# -.net
KiCad netlist of a schematic drawn in Altium Designer
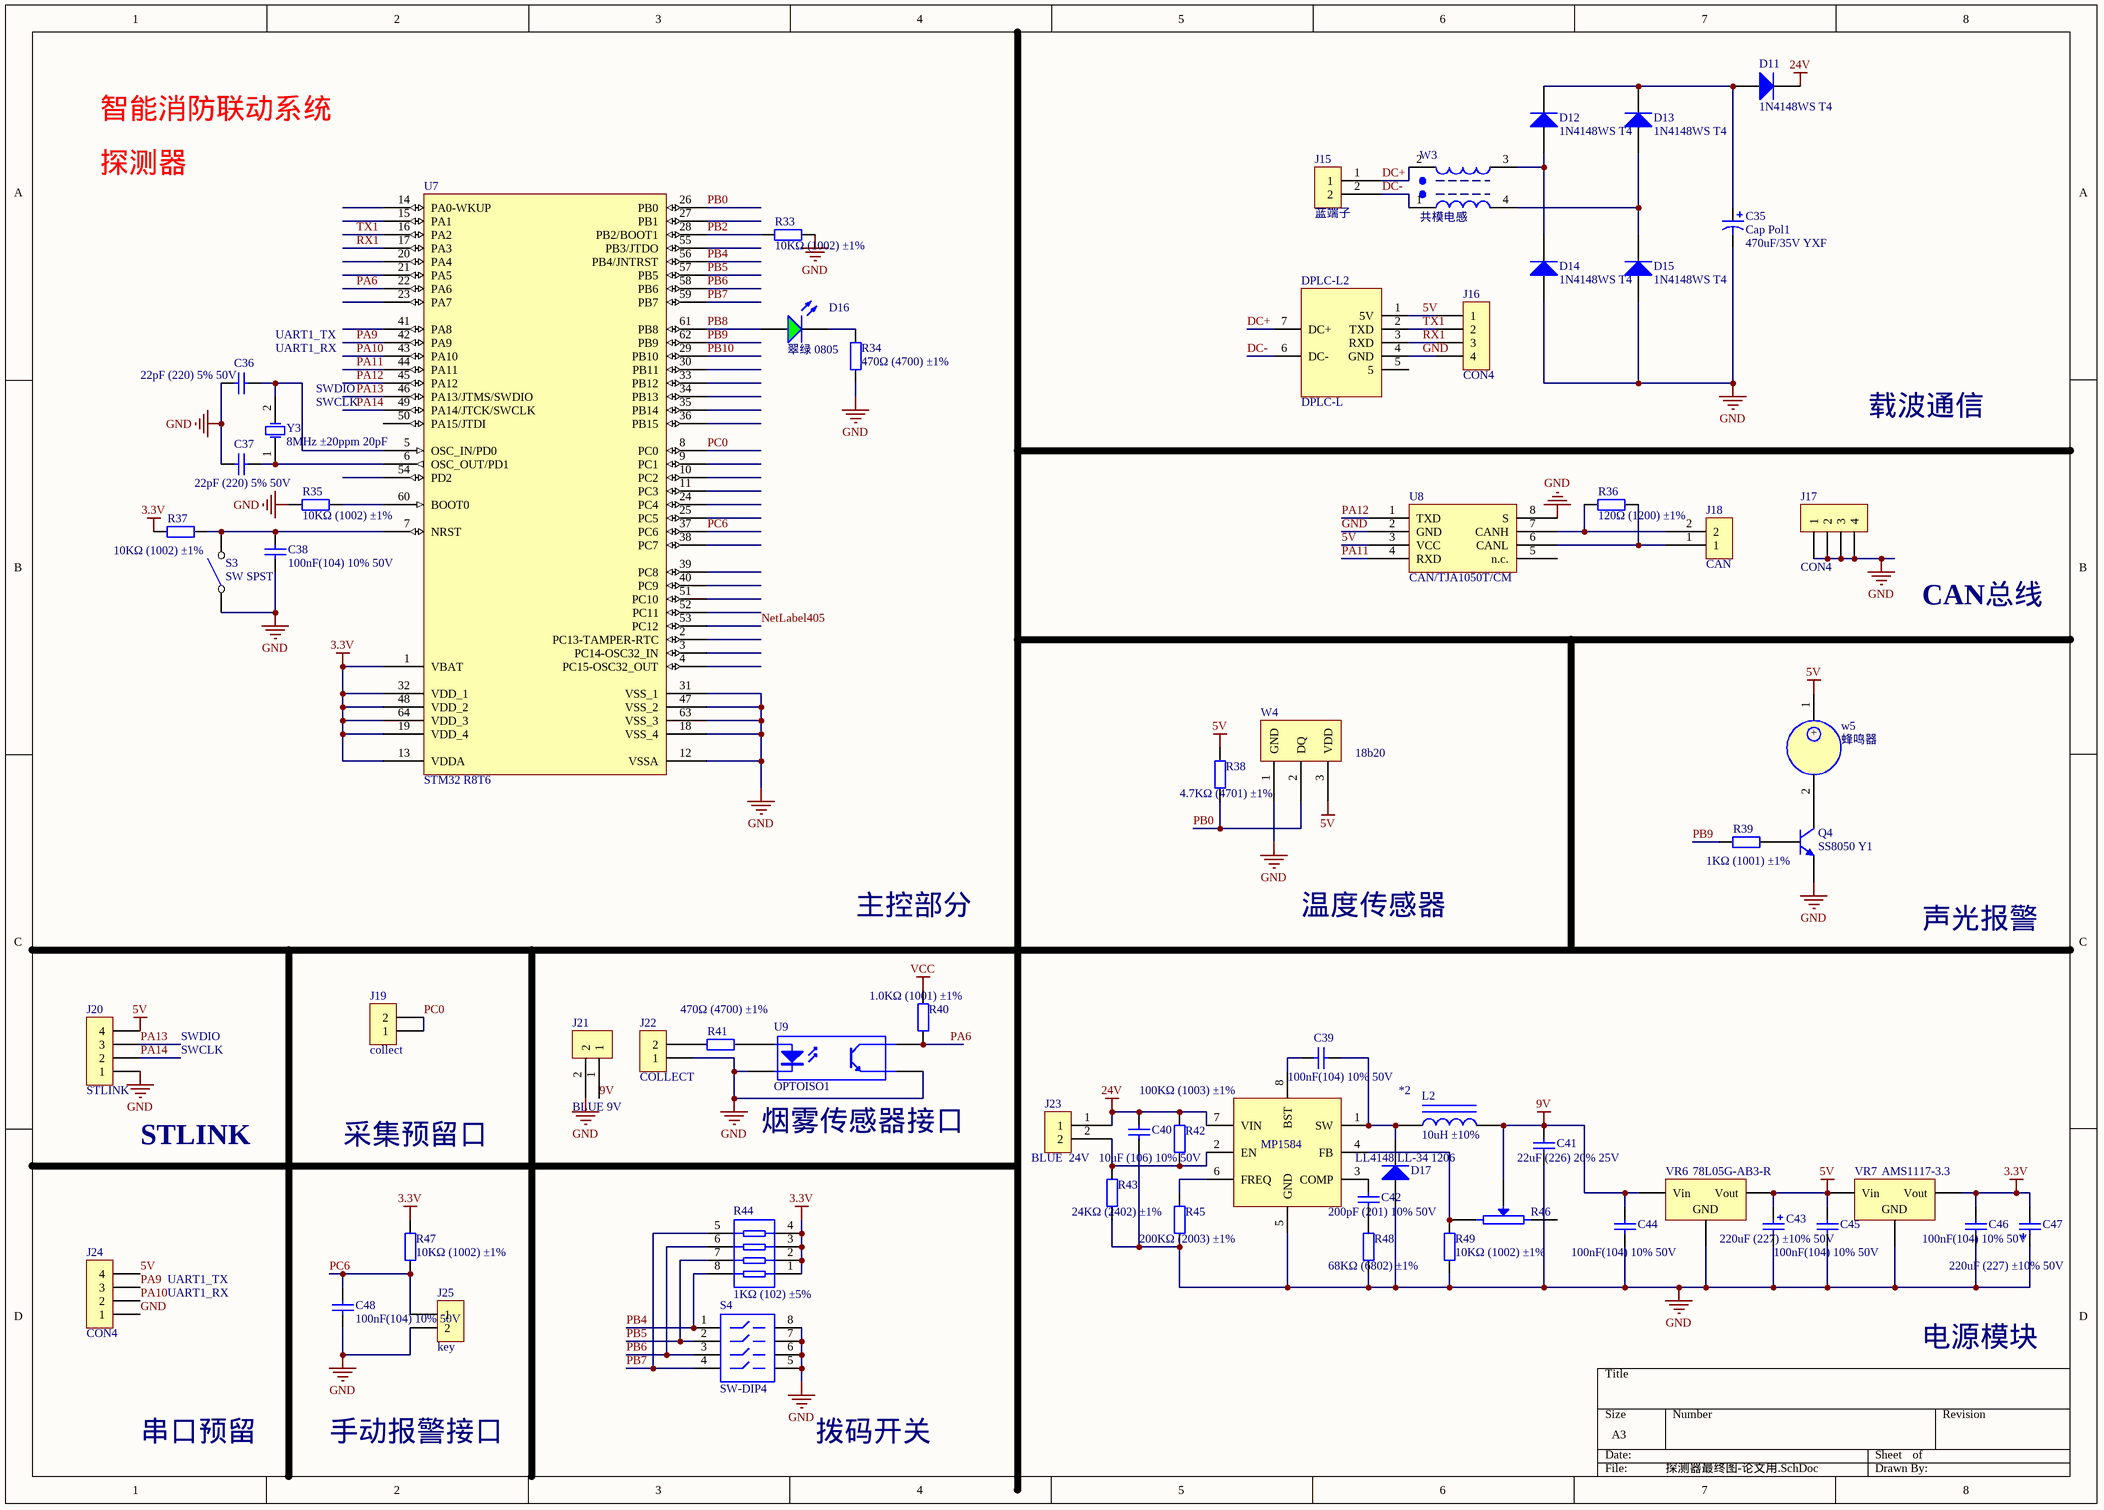
[diagram p0: 探测器最终图-论文用.SchDoc]

(export (version "E")
  (design (tool "Eeschema 10.0.6"))
  (components
    (comp (ref "*2") (value "MP1584") (libsource (lib "毕设原理图封装库") (part "MP1584")))
    (comp (ref "C35")
      (value "Cap Pol1")
      (footprint "RB.2/.4")
      (description "Polarized Capacitor (Radial)")
      (fields (field (name "ALTIUM_VALUE") "470uF/35V YXF") (field (name "PUBLISHER") "Altium Limited"))
      (libsource (lib "Miscellaneous Devices") (part "Cap Pol1"))
    )
    (comp (ref "C36")
      (value "22pF (220) 5% 50V")
      (footprint "LC-0805_C")
      (description "贴片电容")
      (libsource (lib "Miscellaneous Devices LC") (part "0805 22pF (220) 5% 50V"))
    )
    (comp (ref "C37")
      (value "22pF (220) 5% 50V")
      (footprint "LC-0805_C")
      (description "贴片电容")
      (libsource (lib "Miscellaneous Devices LC") (part "0805 22pF (220) 5% 50V"))
    )
    (comp (ref "C38")
      (value "100nF(104) 10% 50V")
      (footprint "LC-0805_C")
      (description "贴片电容")
      (libsource (lib "Miscellaneous Devices LC") (part "0805 100nF(104) 10% 50V"))
    )
    (comp (ref "C39")
      (value "100nF(104) 10% 50V")
      (footprint "LC-0805_C")
      (description "贴片电容")
      (libsource (lib "Miscellaneous Devices LC") (part "0805 100nF(104) 10% 50V"))
    )
    (comp (ref "C40")
      (value "10uF (106) 10% 50V")
      (footprint "LC-1206_C")
      (description "贴片电容")
      (libsource (lib "Miscellaneous Devices LC") (part "1206 10uF (106) 10% 50V"))
    )
    (comp (ref "C41")
      (value "22uF (226) 20% 25V")
      (footprint "LC-0805_C")
      (description "贴片电容")
      (libsource (lib "Miscellaneous Devices LC") (part "0805 22uF (226) 20% 25V"))
    )
    (comp (ref "C42")
      (value "200pF (201) 10% 50V")
      (footprint "LC-0805_C")
      (description "贴片电容")
      (libsource (lib "Miscellaneous Devices LC") (part "0805 200pF (201) 10% 50V"))
    )
    (comp (ref "C43")
      (value "220uF (227) ±10% 50V")
      (footprint "LC-CASE-B_3528")
      (description "钽电容")
      (libsource (lib "Miscellaneous Devices LC") (part "3528 100uF (107) 10% 6.3V"))
    )
    (comp (ref "C44")
      (value "100nF(104) 10% 50V")
      (footprint "LC-0805_C")
      (description "贴片电容")
      (libsource (lib "Miscellaneous Devices LC") (part "0805 100nF(104) 10% 50V"))
    )
    (comp (ref "C45")
      (value "100nF(104) 10% 50V")
      (footprint "LC-0805_C")
      (description "贴片电容")
      (libsource (lib "Miscellaneous Devices LC") (part "0805 100nF(104) 10% 50V"))
    )
    (comp (ref "C46")
      (value "100nF(104) 10% 50V")
      (footprint "LC-0805_C")
      (description "贴片电容")
      (libsource (lib "Miscellaneous Devices LC") (part "0805 100nF(104) 10% 50V"))
    )
    (comp (ref "C47")
      (value "220uF (227) ±10% 50V")
      (footprint "LC-CASE-B_3528")
      (description "钽电容")
      (libsource (lib "Miscellaneous Devices LC") (part "3528 100uF (107) 10% 6.3V"))
    )
    (comp (ref "C48")
      (value "100nF(104) 10% 50V")
      (footprint "LC-0805_C")
      (description "贴片电容")
      (libsource (lib "Miscellaneous Devices LC") (part "0805 100nF(104) 10% 50V"))
    )
    (comp (ref "D11")
      (value "1N4148WS T4")
      (footprint "LC-SOD-323")
      (description "二极管")
      (libsource (lib "Miscellaneous Devices LC") (part "SOD-323 1N4148WS T4"))
    )
    (comp (ref "D12")
      (value "1N4148WS T4")
      (footprint "LC-SOD-323")
      (description "二极管")
      (libsource (lib "Miscellaneous Devices LC") (part "SOD-323 1N4148WS T4"))
    )
    (comp (ref "D13")
      (value "1N4148WS T4")
      (footprint "LC-SOD-323")
      (description "二极管")
      (libsource (lib "Miscellaneous Devices LC") (part "SOD-323 1N4148WS T4"))
    )
    (comp (ref "D14")
      (value "1N4148WS T4")
      (footprint "LC-SOD-323")
      (description "二极管")
      (libsource (lib "Miscellaneous Devices LC") (part "SOD-323 1N4148WS T4"))
    )
    (comp (ref "D15")
      (value "1N4148WS T4")
      (footprint "LC-SOD-323")
      (description "二极管")
      (libsource (lib "Miscellaneous Devices LC") (part "SOD-323 1N4148WS T4"))
    )
    (comp (ref "D16")
      (value "翠绿 0805")
      (footprint "LC-0805_LED_S1")
      (description "发光二极管")
      (libsource (lib "Miscellaneous Devices LC") (part "0805 翠绿"))
    )
    (comp (ref "D17")
      (value "LL4148 LL-34 1206")
      (footprint "LC-LL-34")
      (description "开关二极管")
      (libsource (lib "Miscellaneous Devices LC") (part "LL-34 LL4148 LL-34 1206"))
    )
    (comp (ref "DPLC-L2") (value "DPLC-L") (footprint "DPLC-L") (libsource (lib "毕设原理图封装库") (part "DPLC-L")))
    (comp (ref "J15") (value "蓝端子") (footprint "蓝端子") (libsource (lib "") (part "蓝端子_1")))
    (comp (ref "J16") (value "CON4") (footprint "SIP4") (libsource (lib "") (part "CON4_1")))
    (comp (ref "J17") (value "CON4") (footprint "SIP4") (libsource (lib "") (part "CON4_2")))
    (comp (ref "J18") (value "CAN") (footprint "蓝端子") (libsource (lib "") (part "蓝端子_2")))
    (comp (ref "J19") (value "collect") (footprint "SIP2") (libsource (lib "") (part "CON2_1")))
    (comp (ref "J20") (value "STLINK") (footprint "SIP4") (libsource (lib "毕设原理图封装库") (part "CON4")))
    (comp (ref "J21") (value "BLUE 9V") (footprint "蓝端子") (libsource (lib "毕设原理图封装库") (part "蓝端子")))
    (comp (ref "J22") (value "COLLECT") (footprint "SIP2") (libsource (lib "") (part "CON2_1")))
    (comp (ref "J23") (value "BLUE  24V") (footprint "蓝端子") (libsource (lib "") (part "蓝端子_1")))
    (comp (ref "J24") (value "CON4") (footprint "SIP4") (libsource (lib "毕设原理图封装库") (part "CON4")))
    (comp (ref "J25") (value "key") (footprint "SIP2") (libsource (lib "毕设原理图封装库") (part "CON2")))
    (comp (ref "L2")
      (value "10uH ±10%")
      (footprint "LC-0805_L")
      (description "贴片电感")
      (libsource (lib "Miscellaneous Devices LC") (part "0805 10uH 10%"))
    )
    (comp (ref "Q4")
      (value "SS8050 Y1")
      (footprint "LC-SOT-23(SOT-23-3)")
      (description "三极管")
      (libsource (lib "Miscellaneous Devices LC") (part "SOT-23 SS8050 Y1"))
    )
    (comp (ref "R33")
      (value "10KΩ (1002) ±1%")
      (footprint "LC-0805_R")
      (description "贴片电阻")
      (libsource (lib "") (part "0805 10KΩ (1002) 1%_2"))
    )
    (comp (ref "R34")
      (value "470Ω (4700) ±1%")
      (footprint "LC-0805_R")
      (description "贴片电阻")
      (libsource (lib "Miscellaneous Devices LC") (part "0805 470Ω (4700) 1%"))
    )
    (comp (ref "R35")
      (value "10KΩ (1002) ±1%")
      (footprint "LC-0805_R")
      (description "贴片电阻")
      (libsource (lib "Miscellaneous Devices LC") (part "0805 10KΩ (1002) 1%"))
    )
    (comp (ref "R36")
      (value "120Ω (1200) ±1%")
      (footprint "LC-0805_R")
      (description "贴片电阻")
      (libsource (lib "Miscellaneous Devices LC") (part "0805 120Ω (1200) 1%"))
    )
    (comp (ref "R37")
      (value "10KΩ (1002) ±1%")
      (footprint "LC-0805_R")
      (description "贴片电阻")
      (libsource (lib "Miscellaneous Devices LC") (part "0805 10KΩ (1002) 1%"))
    )
    (comp (ref "R38")
      (value "4.7KΩ (4701) ±1%")
      (footprint "LC-0805_R")
      (description "贴片电阻")
      (libsource (lib "") (part "0805 4.7KΩ (4701) 1%_1"))
    )
    (comp (ref "R39")
      (value "1KΩ (1001) ±1%")
      (footprint "LC-0805_R")
      (description "贴片电阻")
      (libsource (lib "Miscellaneous Devices LC") (part "0805 1KΩ (1001) 1%"))
    )
    (comp (ref "R40")
      (value "1.0KΩ (1001) ±1%")
      (footprint "LC-0805_R")
      (description "贴片电阻")
      (libsource (lib "") (part "0805 4.7KΩ (4701) 1%_1"))
    )
    (comp (ref "R41")
      (value "470Ω (4700) ±1%")
      (footprint "LC-0805_R")
      (description "贴片电阻")
      (libsource (lib "Miscellaneous Devices LC") (part "0805 4.7KΩ (4701) 1%"))
    )
    (comp (ref "R42")
      (value "100KΩ (1003) ±1%")
      (footprint "LC-0805_R")
      (description "贴片电阻")
      (libsource (lib "Miscellaneous Devices LC") (part "0805 100KΩ (1003) 1%"))
    )
    (comp (ref "R43")
      (value "24KΩ (2402) ±1%")
      (footprint "LC-0805_R")
      (description "贴片电阻")
      (libsource (lib "Miscellaneous Devices LC") (part "0805 24KΩ (2402) 1%"))
    )
    (comp (ref "R44")
      (value "1KΩ (102) ±5%")
      (footprint "LC-0603_Rx4")
      (description "贴片排阻")
      (libsource (lib "Miscellaneous Devices LC") (part "0603*4  1KΩ (102) 5%"))
    )
    (comp (ref "R45")
      (value "200KΩ (2003) ±1%")
      (footprint "LC-0805_R")
      (description "贴片电阻")
      (libsource (lib "Miscellaneous Devices LC") (part "0805 200KΩ (2003) 1%"))
    )
    (comp (ref "R46") (value "2") (description "滑变2") (libsource (lib "原理图封装库") (part "POT2")))
    (comp (ref "R47")
      (value "10KΩ (1002) ±1%")
      (footprint "LC-0805_R")
      (description "贴片电阻")
      (libsource (lib "") (part "0805 10KΩ (1002) 1%_1"))
    )
    (comp (ref "R48")
      (value "68KΩ (6802) ±1%")
      (footprint "LC-0805_R")
      (description "贴片电阻")
      (libsource (lib "Miscellaneous Devices LC") (part "0805 68KΩ (6802) 1%"))
    )
    (comp (ref "R49")
      (value "10KΩ (1002) ±1%")
      (footprint "LC-0805_R")
      (description "贴片电阻")
      (libsource (lib "") (part "0805 10KΩ (1002) 1%_1"))
    )
    (comp (ref "S3")
      (value "SW SPST")
      (footprint "单片机小按键")
      (description "单刀单掷开关")
      (libsource (lib "毕设原理图封装库") (part "SW SPST"))
    )
    (comp (ref "S4")
      (value "SW-DIP4")
      (footprint "4位拨码开关")
      (description "4位拨码开关")
      (libsource (lib "毕设原理图封装库") (part "SW-DIP4"))
    )
    (comp (ref "U7")
      (value "STM32 R8T6")
      (footprint "LC-LQFP-64_10x10x05P")
      (libsource (lib "毕设原理图封装库") (part "STM32 R8T6"))
    )
    (comp (ref "U8")
      (value "CAN/TJA1050T/CM")
      (footprint "LC-SOIC-8_150mil")
      (description "CAN")
      (libsource (lib "Miscellaneous Devices LC") (part "CAN/TJA1050T/CM"))
    )
    (comp (ref "U9")
      (value "OPTOISO1")
      (footprint "LC-SOP-4_P2.54")
      (description "光电对管")
      (libsource (lib "毕设原理图封装库") (part "OPTOISO1"))
    )
    (comp (ref "VR6")
      (value "78L05G-AB3-R")
      (footprint "LC-SOT-89(SOT-89-3)")
      (description "低压差线性稳压(LDO)")
      (libsource (lib "Miscellaneous Devices LC") (part "SOT-89 78L05G-AB3-R"))
    )
    (comp (ref "VR7")
      (value "AMS1117-3.3")
      (footprint "LC-SOT-223")
      (description "低压差线性稳压(LDO)")
      (libsource (lib "Miscellaneous Devices LC") (part "SOT-223 AMS1117-3.3"))
    )
    (comp (ref "W3") (value "共模电感") (footprint "共模电感") (libsource (lib "毕设原理图封装库") (part "共模电感")))
    (comp (ref "W4") (value "18b20") (footprint "DS18B20") (libsource (lib "毕设原理图封装库") (part "18b20")))
    (comp (ref "w5") (value "蜂鸣器") (footprint "蜂鸣器") (libsource (lib "毕设原理图封装库") (part "蜂鸣器")))
    (comp (ref "Y3")
      (value "8MHz ±20ppm 20pF")
      (footprint "LC-SMD-5032_2P")
      (description "贴片晶振")
      (libsource (lib "Miscellaneous Devices LC") (part "SMD-5032_2P 8MHz 20ppm 20pF"))
    )
  )
  (nets
    (net (code "1") (name "/DC+") (class "Default")
      (node (ref "DPLC-L2") (pin "7") (pinfunction "DC+_7") (pintype "passive"))
      (node (ref "J15") (pin "1") (pinfunction "1_1") (pintype "passive"))
      (node (ref "W3") (pin "2") (pinfunction "2_2") (pintype "passive"))
    )
    (net (code "2") (name "/DC-") (class "Default")
      (node (ref "DPLC-L2") (pin "6") (pinfunction "DC-_6") (pintype "passive"))
      (node (ref "J15") (pin "2") (pinfunction "2_2") (pintype "passive"))
      (node (ref "W3") (pin "1") (pinfunction "1_1") (pintype "passive"))
    )
    (net (code "3") (name "/NetLabel405") (class "Default")
      (node (ref "U7") (pin "53") (pinfunction "PC12_53") (pintype "bidirectional"))
    )
    (net (code "4") (name "/PA6") (class "Default")
      (node (ref "R40") (pin "1") (pinfunction "1_1") (pintype "passive"))
      (node (ref "U7") (pin "22") (pinfunction "PA6_22") (pintype "bidirectional"))
      (node (ref "U9") (pin "4") (pinfunction "C_4") (pintype "passive"))
    )
    (net (code "5") (name "/PA9") (class "Default")
      (node (ref "J24") (pin "3") (pinfunction "3_3") (pintype "passive"))
      (node (ref "U7") (pin "42") (pinfunction "PA9_42") (pintype "bidirectional"))
    )
    (net (code "6") (name "/PA10") (class "Default")
      (node (ref "J24") (pin "2") (pinfunction "2_2") (pintype "passive"))
      (node (ref "U7") (pin "43") (pinfunction "PA10_43") (pintype "bidirectional"))
    )
    (net (code "7") (name "/PA11") (class "Default")
      (node (ref "U7") (pin "44") (pinfunction "PA11_44") (pintype "bidirectional"))
      (node (ref "U8") (pin "4") (pinfunction "RXD_4") (pintype "passive"))
    )
    (net (code "8") (name "/PA12") (class "Default")
      (node (ref "U7") (pin "45") (pinfunction "PA12_45") (pintype "bidirectional"))
      (node (ref "U8") (pin "1") (pinfunction "TXD_1") (pintype "passive"))
    )
    (net (code "9") (name "/PA13") (class "Default")
      (node (ref "J20") (pin "3") (pinfunction "3_3") (pintype "passive"))
      (node (ref "U7") (pin "46") (pinfunction "PA13/JTMS/SWDIO_46") (pintype "bidirectional"))
    )
    (net (code "10") (name "/PA14") (class "Default")
      (node (ref "J20") (pin "2") (pinfunction "2_2") (pintype "passive"))
      (node (ref "U7") (pin "49") (pinfunction "PA14/JTCK/SWCLK_49") (pintype "bidirectional"))
    )
    (net (code "11") (name "/PB0") (class "Default")
      (node (ref "R38") (pin "1") (pinfunction "1_1") (pintype "passive"))
      (node (ref "U7") (pin "26") (pinfunction "PB0_26") (pintype "bidirectional"))
      (node (ref "W4") (pin "2") (pinfunction "DQ_2") (pintype "passive"))
    )
    (net (code "12") (name "/PB2") (class "Default")
      (node (ref "R33") (pin "2") (pinfunction "2_2") (pintype "passive"))
      (node (ref "U7") (pin "28") (pinfunction "PB2/BOOT1_28") (pintype "bidirectional"))
    )
    (net (code "13") (name "/PB4") (class "Default")
      (node (ref "R44") (pin "8") (pinfunction "8_8") (pintype "passive"))
      (node (ref "S4") (pin "1") (pinfunction "1_1") (pintype "passive"))
      (node (ref "U7") (pin "56") (pinfunction "PB4/JNTRST_56") (pintype "bidirectional"))
    )
    (net (code "14") (name "/PB5") (class "Default")
      (node (ref "R44") (pin "7") (pinfunction "7_7") (pintype "passive"))
      (node (ref "S4") (pin "2") (pinfunction "2_2") (pintype "passive"))
      (node (ref "U7") (pin "57") (pinfunction "PB5_57") (pintype "bidirectional"))
    )
    (net (code "15") (name "/PB6") (class "Default")
      (node (ref "R44") (pin "6") (pinfunction "6_6") (pintype "passive"))
      (node (ref "S4") (pin "3") (pinfunction "3_3") (pintype "passive"))
      (node (ref "U7") (pin "58") (pinfunction "PB6_58") (pintype "bidirectional"))
    )
    (net (code "16") (name "/PB7") (class "Default")
      (node (ref "R44") (pin "5") (pinfunction "5_5") (pintype "passive"))
      (node (ref "S4") (pin "4") (pinfunction "4_4") (pintype "passive"))
      (node (ref "U7") (pin "59") (pinfunction "PB7_59") (pintype "bidirectional"))
    )
    (net (code "17") (name "/PB8") (class "Default")
      (node (ref "D16") (pin "A") (pinfunction "A_A") (pintype "passive"))
      (node (ref "U7") (pin "61") (pinfunction "PB8_61") (pintype "bidirectional"))
    )
    (net (code "18") (name "/PB9") (class "Default")
      (node (ref "R39") (pin "1") (pinfunction "1_1") (pintype "passive"))
      (node (ref "U7") (pin "62") (pinfunction "PB9_62") (pintype "bidirectional"))
    )
    (net (code "19") (name "/PB10") (class "Default")
      (node (ref "U7") (pin "29") (pinfunction "PB10_29") (pintype "bidirectional"))
    )
    (net (code "20") (name "/PC0") (class "Default")
      (node (ref "J19") (pin "1") (pinfunction "1_1") (pintype "passive"))
      (node (ref "J19") (pin "2") (pinfunction "2_2") (pintype "passive"))
      (node (ref "U7") (pin "8") (pinfunction "PC0_8") (pintype "bidirectional"))
    )
    (net (code "21") (name "/PC6") (class "Default")
      (node (ref "C48") (pin "2") (pinfunction "2_2") (pintype "passive"))
      (node (ref "J25") (pin "1") (pinfunction "1_1") (pintype "passive"))
      (node (ref "R47") (pin "1") (pinfunction "1_1") (pintype "passive"))
      (node (ref "U7") (pin "37") (pinfunction "PC6_37") (pintype "bidirectional"))
    )
    (net (code "22") (name "/RX1") (class "Default")
      (node (ref "DPLC-L2") (pin "3") (pinfunction "RXD_3") (pintype "passive"))
      (node (ref "J16") (pin "3") (pinfunction "3_3") (pintype "passive"))
      (node (ref "U7") (pin "17") (pinfunction "PA3_17") (pintype "bidirectional"))
    )
    (net (code "23") (name "/TX1") (class "Default")
      (node (ref "DPLC-L2") (pin "2") (pinfunction "TXD_2") (pintype "passive"))
      (node (ref "J16") (pin "2") (pinfunction "2_2") (pintype "passive"))
      (node (ref "U7") (pin "16") (pinfunction "PA2_16") (pintype "bidirectional"))
    )
    (net (code "24") (name "3.3V") (class "Default")
      (node (ref "C46") (pin "1") (pinfunction "1_1") (pintype "passive"))
      (node (ref "C47") (pin "2") (pinfunction "2_2") (pintype "passive"))
      (node (ref "R37") (pin "1") (pinfunction "1_1") (pintype "passive"))
      (node (ref "R44") (pin "1") (pinfunction "1_1") (pintype "passive"))
      (node (ref "R44") (pin "2") (pinfunction "2_2") (pintype "passive"))
      (node (ref "R44") (pin "3") (pinfunction "3_3") (pintype "passive"))
      (node (ref "R44") (pin "4") (pinfunction "4_4") (pintype "passive"))
      (node (ref "R47") (pin "2") (pinfunction "2_2") (pintype "passive"))
      (node (ref "U7") (pin "1") (pinfunction "VBAT_1") (pintype "power_in"))
      (node (ref "U7") (pin "13") (pinfunction "VDDA_13") (pintype "power_in"))
      (node (ref "U7") (pin "19") (pinfunction "VDD_4_19") (pintype "power_in"))
      (node (ref "U7") (pin "32") (pinfunction "VDD_1_32") (pintype "power_in"))
      (node (ref "U7") (pin "48") (pinfunction "VDD_2_48") (pintype "power_in"))
      (node (ref "U7") (pin "64") (pinfunction "VDD_3_64") (pintype "power_in"))
      (node (ref "VR7") (pin "2") (pinfunction "Vout_2") (pintype "passive"))
    )
    (net (code "25") (name "5V") (class "Default")
      (node (ref "C43") (pin "1") (pinfunction "1_1") (pintype "passive"))
      (node (ref "C45") (pin "2") (pinfunction "2_2") (pintype "passive"))
      (node (ref "DPLC-L2") (pin "1") (pinfunction "5V_1") (pintype "passive"))
      (node (ref "J16") (pin "1") (pinfunction "1_1") (pintype "passive"))
      (node (ref "J20") (pin "4") (pinfunction "4_4") (pintype "passive"))
      (node (ref "J24") (pin "4") (pinfunction "4_4") (pintype "passive"))
      (node (ref "R38") (pin "2") (pinfunction "2_2") (pintype "passive"))
      (node (ref "U8") (pin "3") (pinfunction "VCC_3") (pintype "passive"))
      (node (ref "VR6") (pin "3") (pinfunction "Vout_3") (pintype "passive"))
      (node (ref "VR7") (pin "3") (pinfunction "Vin_3") (pintype "passive"))
      (node (ref "W4") (pin "3") (pinfunction "VDD_3") (pintype "passive"))
      (node (ref "w5") (pin "1") (pinfunction "+_1") (pintype "passive"))
    )
    (net (code "26") (name "9V") (class "Default")
      (node (ref "C41") (pin "2") (pinfunction "2_2") (pintype "passive"))
      (node (ref "C44") (pin "2") (pinfunction "2_2") (pintype "passive"))
      (node (ref "J21") (pin "1") (pinfunction "1_1") (pintype "passive"))
      (node (ref "L2") (pin "2") (pinfunction "2_2") (pintype "passive"))
      (node (ref "R46") (pin "3") (pinfunction "W_3") (pintype "passive"))
      (node (ref "VR6") (pin "1") (pinfunction "Vin_1") (pintype "passive"))
    )
    (net (code "27") (name "24V") (class "Default")
      (node (ref "*2") (pin "7") (pinfunction "VIN_7") (pintype "passive"))
      (node (ref "C40") (pin "2") (pinfunction "2_2") (pintype "passive"))
      (node (ref "D11") (pin "2") (pinfunction "K_2") (pintype "passive"))
      (node (ref "J23") (pin "1") (pinfunction "1_1") (pintype "passive"))
      (node (ref "R42") (pin "2") (pinfunction "2_2") (pintype "passive"))
    )
    (net (code "28") (name "GND") (class "Default")
      (node (ref "*2") (pin "5") (pinfunction "GND_5") (pintype "passive"))
      (node (ref "C35") (pin "2") (pinfunction "2_2") (pintype "passive"))
      (node (ref "C36") (pin "1") (pinfunction "1_1") (pintype "passive"))
      (node (ref "C37") (pin "1") (pinfunction "1_1") (pintype "passive"))
      (node (ref "C38") (pin "1") (pinfunction "1_1") (pintype "passive"))
      (node (ref "C40") (pin "1") (pinfunction "1_1") (pintype "passive"))
      (node (ref "C41") (pin "1") (pinfunction "1_1") (pintype "passive"))
      (node (ref "C43") (pin "2") (pinfunction "2_2") (pintype "passive"))
      (node (ref "C44") (pin "1") (pinfunction "1_1") (pintype "passive"))
      (node (ref "C45") (pin "1") (pinfunction "1_1") (pintype "passive"))
      (node (ref "C46") (pin "2") (pinfunction "2_2") (pintype "passive"))
      (node (ref "C47") (pin "1") (pinfunction "1_1") (pintype "passive"))
      (node (ref "C48") (pin "1") (pinfunction "1_1") (pintype "passive"))
      (node (ref "D14") (pin "1") (pinfunction "A_1") (pintype "passive"))
      (node (ref "D15") (pin "1") (pinfunction "A_1") (pintype "passive"))
      (node (ref "D17") (pin "1") (pinfunction "A_1") (pintype "passive"))
      (node (ref "DPLC-L2") (pin "4") (pinfunction "GND_4") (pintype "passive"))
      (node (ref "J16") (pin "4") (pinfunction "4_4") (pintype "passive"))
      (node (ref "J17") (pin "1") (pinfunction "1_1") (pintype "passive"))
      (node (ref "J17") (pin "2") (pinfunction "2_2") (pintype "passive"))
      (node (ref "J17") (pin "3") (pinfunction "3_3") (pintype "passive"))
      (node (ref "J17") (pin "4") (pinfunction "4_4") (pintype "passive"))
      (node (ref "J20") (pin "1") (pinfunction "1_1") (pintype "passive"))
      (node (ref "J21") (pin "2") (pinfunction "2_2") (pintype "passive"))
      (node (ref "J22") (pin "1") (pinfunction "1_1") (pintype "passive"))
      (node (ref "J24") (pin "1") (pinfunction "1_1") (pintype "passive"))
      (node (ref "J25") (pin "2") (pinfunction "2_2") (pintype "passive"))
      (node (ref "Q4") (pin "2") (pinfunction "E_2") (pintype "passive"))
      (node (ref "R33") (pin "1") (pinfunction "1_1") (pintype "passive"))
      (node (ref "R34") (pin "1") (pinfunction "1_1") (pintype "passive"))
      (node (ref "R35") (pin "1") (pinfunction "1_1") (pintype "passive"))
      (node (ref "R43") (pin "1") (pinfunction "1_1") (pintype "passive"))
      (node (ref "R45") (pin "1") (pinfunction "1_1") (pintype "passive"))
      (node (ref "R48") (pin "1") (pinfunction "1_1") (pintype "passive"))
      (node (ref "R49") (pin "1") (pinfunction "1_1") (pintype "passive"))
      (node (ref "S3") (pin "1") (pinfunction "COMMON_1") (pintype "passive"))
      (node (ref "S4") (pin "5") (pinfunction "5_5") (pintype "passive"))
      (node (ref "S4") (pin "6") (pinfunction "6_6") (pintype "passive"))
      (node (ref "S4") (pin "7") (pinfunction "7_7") (pintype "passive"))
      (node (ref "S4") (pin "8") (pinfunction "8_8") (pintype "passive"))
      (node (ref "U7") (pin "12") (pinfunction "VSSA_12") (pintype "power_in"))
      (node (ref "U7") (pin "18") (pinfunction "VSS_4_18") (pintype "power_in"))
      (node (ref "U7") (pin "31") (pinfunction "VSS_1_31") (pintype "power_in"))
      (node (ref "U7") (pin "47") (pinfunction "VSS_2_47") (pintype "power_in"))
      (node (ref "U7") (pin "63") (pinfunction "VSS_3_63") (pintype "power_in"))
      (node (ref "U8") (pin "2") (pinfunction "GND_2") (pintype "passive"))
      (node (ref "U8") (pin "8") (pinfunction "S_8") (pintype "passive"))
      (node (ref "U9") (pin "2") (pinfunction "K_2") (pintype "passive"))
      (node (ref "U9") (pin "3") (pinfunction "E_3") (pintype "passive"))
      (node (ref "VR6") (pin "2") (pinfunction "GND_2") (pintype "passive"))
      (node (ref "VR7") (pin "1") (pinfunction "GND_1") (pintype "passive"))
      (node (ref "W4") (pin "1") (pinfunction "GND_1") (pintype "passive"))
    )
    (net (code "29") (name "Net-(*2-BST)") (class "Default")
      (node (ref "*2") (pin "8") (pinfunction "BST_8") (pintype "passive"))
      (node (ref "C39") (pin "1") (pinfunction "1_1") (pintype "passive"))
    )
    (net (code "30") (name "Net-(*2-COMP)") (class "Default")
      (node (ref "*2") (pin "3") (pinfunction "COMP_3") (pintype "passive"))
      (node (ref "C42") (pin "2") (pinfunction "2_2") (pintype "passive"))
    )
    (net (code "31") (name "Net-(*2-EN)") (class "Default")
      (node (ref "*2") (pin "2") (pinfunction "EN_2") (pintype "passive"))
      (node (ref "J23") (pin "2") (pinfunction "2_2") (pintype "passive"))
      (node (ref "R42") (pin "1") (pinfunction "1_1") (pintype "passive"))
      (node (ref "R43") (pin "2") (pinfunction "2_2") (pintype "passive"))
    )
    (net (code "32") (name "Net-(*2-FB)") (class "Default")
      (node (ref "*2") (pin "4") (pinfunction "FB_4") (pintype "passive"))
      (node (ref "R46") (pin "1") (pinfunction "1_1") (pintype "passive"))
      (node (ref "R49") (pin "2") (pinfunction "2_2") (pintype "passive"))
    )
    (net (code "33") (name "Net-(*2-FREQ)") (class "Default")
      (node (ref "*2") (pin "6") (pinfunction "FREQ_6") (pintype "passive"))
      (node (ref "R45") (pin "2") (pinfunction "2_2") (pintype "passive"))
    )
    (net (code "34") (name "Net-(*2-SW)") (class "Default")
      (node (ref "*2") (pin "1") (pinfunction "SW_1") (pintype "passive"))
      (node (ref "C39") (pin "2") (pinfunction "2_2") (pintype "passive"))
      (node (ref "D17") (pin "2") (pinfunction "K_2") (pintype "passive"))
      (node (ref "L2") (pin "1") (pinfunction "1_1") (pintype "passive"))
    )
    (net (code "35") (name "Net-(C42-Pad1)") (class "Default")
      (node (ref "C42") (pin "1") (pinfunction "1_1") (pintype "passive"))
      (node (ref "R48") (pin "2") (pinfunction "2_2") (pintype "passive"))
    )
    (net (code "36") (name "Net-(D11-A)") (class "Default")
      (node (ref "C35") (pin "1") (pinfunction "1_1") (pintype "passive"))
      (node (ref "D11") (pin "1") (pinfunction "A_1") (pintype "passive"))
      (node (ref "D12") (pin "2") (pinfunction "K_2") (pintype "passive"))
      (node (ref "D13") (pin "2") (pinfunction "K_2") (pintype "passive"))
    )
    (net (code "37") (name "Net-(D12-A)") (class "Default")
      (node (ref "D12") (pin "1") (pinfunction "A_1") (pintype "passive"))
      (node (ref "D14") (pin "2") (pinfunction "K_2") (pintype "passive"))
      (node (ref "W3") (pin "3") (pinfunction "3_3") (pintype "passive"))
    )
    (net (code "38") (name "Net-(D13-A)") (class "Default")
      (node (ref "D13") (pin "1") (pinfunction "A_1") (pintype "passive"))
      (node (ref "D15") (pin "2") (pinfunction "K_2") (pintype "passive"))
      (node (ref "W3") (pin "4") (pinfunction "4_4") (pintype "passive"))
    )
    (net (code "39") (name "Net-(D16-PadK)") (class "Default")
      (node (ref "D16") (pin "K") (pinfunction "K_K") (pintype "passive"))
      (node (ref "R34") (pin "2") (pinfunction "2_2") (pintype "passive"))
    )
    (net (code "40") (name "Net-(J22-Pad2)") (class "Default")
      (node (ref "J22") (pin "2") (pinfunction "2_2") (pintype "passive"))
      (node (ref "R41") (pin "2") (pinfunction "2_2") (pintype "passive"))
    )
    (net (code "41") (name "Net-(Q4-B)") (class "Default")
      (node (ref "Q4") (pin "1") (pinfunction "B_1") (pintype "passive"))
      (node (ref "R39") (pin "2") (pinfunction "2_2") (pintype "passive"))
    )
    (net (code "42") (name "Net-(Q4-C)") (class "Default")
      (node (ref "Q4") (pin "3") (pinfunction "C_3") (pintype "passive"))
      (node (ref "w5") (pin "2") (pintype "passive"))
    )
    (net (code "43") (name "Net-(S3-NO)") (class "Default")
      (node (ref "C38") (pin "2") (pinfunction "2_2") (pintype "passive"))
      (node (ref "R37") (pin "2") (pinfunction "2_2") (pintype "passive"))
      (node (ref "S3") (pin "2") (pinfunction "NO_2") (pintype "passive"))
      (node (ref "U7") (pin "7") (pinfunction "NRST_7") (pintype "bidirectional"))
    )
    (net (code "44") (name "Net-(U7-BOOT0)") (class "Default")
      (node (ref "R35") (pin "2") (pinfunction "2_2") (pintype "passive"))
      (node (ref "U7") (pin "60") (pinfunction "BOOT0_60") (pintype "input"))
    )
    (net (code "45") (name "Net-(U7-OSC_IN{slash}PD0)") (class "Default")
      (node (ref "C36") (pin "2") (pinfunction "2_2") (pintype "passive"))
      (node (ref "U7") (pin "5") (pinfunction "OSC_IN/PD0_5") (pintype "input"))
      (node (ref "Y3") (pin "2") (pinfunction "OSC2_2") (pintype "passive"))
    )
    (net (code "46") (name "Net-(U7-OSC_OUT{slash}PD1)") (class "Default")
      (node (ref "C37") (pin "2") (pinfunction "2_2") (pintype "passive"))
      (node (ref "U7") (pin "6") (pinfunction "OSC_OUT/PD1_6") (pintype "output"))
      (node (ref "Y3") (pin "1") (pinfunction "OSC1_1") (pintype "passive"))
    )
    (net (code "47") (name "Net-(U8-CANH)") (class "Default")
      (node (ref "J18") (pin "2") (pinfunction "2_2") (pintype "passive"))
      (node (ref "R36") (pin "1") (pinfunction "1_1") (pintype "passive"))
      (node (ref "U8") (pin "7") (pinfunction "CANH_7") (pintype "passive"))
    )
    (net (code "48") (name "Net-(U8-CANL)") (class "Default")
      (node (ref "J18") (pin "1") (pinfunction "1_1") (pintype "passive"))
      (node (ref "R36") (pin "2") (pinfunction "2_2") (pintype "passive"))
      (node (ref "U8") (pin "6") (pinfunction "CANL_6") (pintype "passive"))
    )
    (net (code "49") (name "Net-(U9-A)") (class "Default")
      (node (ref "R41") (pin "1") (pinfunction "1_1") (pintype "passive"))
      (node (ref "U9") (pin "1") (pinfunction "A_1") (pintype "passive"))
    )
    (net (code "50") (name "VCC") (class "Default")
      (node (ref "R40") (pin "2") (pinfunction "2_2") (pintype "passive"))
    )
    (net (code "51") (name "unconnected-(DPLC-L2-Pad5)") (class "Default")
      (node (ref "DPLC-L2") (pin "5") (pinfunction "5_5") (pintype "passive"))
    )
    (net (code "52") (name "unconnected-(R46-Pad2)") (class "Default")
      (node (ref "R46") (pin "2") (pinfunction "2_2") (pintype "passive"))
    )
    (net (code "53") (name "unconnected-(U7-PA0-WKUP-Pad14)") (class "Default")
      (node (ref "U7") (pin "14") (pinfunction "PA0-WKUP_14") (pintype "bidirectional"))
    )
    (net (code "54") (name "unconnected-(U7-PA1-Pad15)") (class "Default")
      (node (ref "U7") (pin "15") (pinfunction "PA1_15") (pintype "bidirectional"))
    )
    (net (code "55") (name "unconnected-(U7-PA4-Pad20)") (class "Default")
      (node (ref "U7") (pin "20") (pinfunction "PA4_20") (pintype "bidirectional"))
    )
    (net (code "56") (name "unconnected-(U7-PA5-Pad21)") (class "Default")
      (node (ref "U7") (pin "21") (pinfunction "PA5_21") (pintype "bidirectional"))
    )
    (net (code "57") (name "unconnected-(U7-PA7-Pad23)") (class "Default")
      (node (ref "U7") (pin "23") (pinfunction "PA7_23") (pintype "bidirectional"))
    )
    (net (code "58") (name "unconnected-(U7-PA8-Pad41)") (class "Default")
      (node (ref "U7") (pin "41") (pinfunction "PA8_41") (pintype "bidirectional"))
    )
    (net (code "59") (name "unconnected-(U7-PA15{slash}JTDI-Pad50)") (class "Default")
      (node (ref "U7") (pin "50") (pinfunction "PA15/JTDI_50") (pintype "bidirectional"))
    )
    (net (code "60") (name "unconnected-(U7-PB1-Pad27)") (class "Default")
      (node (ref "U7") (pin "27") (pinfunction "PB1_27") (pintype "bidirectional"))
    )
    (net (code "61") (name "unconnected-(U7-PB3{slash}JTDO-Pad55)") (class "Default")
      (node (ref "U7") (pin "55") (pinfunction "PB3/JTDO_55") (pintype "bidirectional"))
    )
    (net (code "62") (name "unconnected-(U7-PB11-Pad30)") (class "Default")
      (node (ref "U7") (pin "30") (pinfunction "PB11_30") (pintype "bidirectional"))
    )
    (net (code "63") (name "unconnected-(U7-PB12-Pad33)") (class "Default")
      (node (ref "U7") (pin "33") (pinfunction "PB12_33") (pintype "bidirectional"))
    )
    (net (code "64") (name "unconnected-(U7-PB13-Pad34)") (class "Default")
      (node (ref "U7") (pin "34") (pinfunction "PB13_34") (pintype "bidirectional"))
    )
    (net (code "65") (name "unconnected-(U7-PB14-Pad35)") (class "Default")
      (node (ref "U7") (pin "35") (pinfunction "PB14_35") (pintype "bidirectional"))
    )
    (net (code "66") (name "unconnected-(U7-PB15-Pad36)") (class "Default")
      (node (ref "U7") (pin "36") (pinfunction "PB15_36") (pintype "bidirectional"))
    )
    (net (code "67") (name "unconnected-(U7-PC1-Pad9)") (class "Default")
      (node (ref "U7") (pin "9") (pinfunction "PC1_9") (pintype "bidirectional"))
    )
    (net (code "68") (name "unconnected-(U7-PC2-Pad10)") (class "Default")
      (node (ref "U7") (pin "10") (pinfunction "PC2_10") (pintype "bidirectional"))
    )
    (net (code "69") (name "unconnected-(U7-PC3-Pad11)") (class "Default")
      (node (ref "U7") (pin "11") (pinfunction "PC3_11") (pintype "bidirectional"))
    )
    (net (code "70") (name "unconnected-(U7-PC4-Pad24)") (class "Default")
      (node (ref "U7") (pin "24") (pinfunction "PC4_24") (pintype "bidirectional"))
    )
    (net (code "71") (name "unconnected-(U7-PC5-Pad25)") (class "Default")
      (node (ref "U7") (pin "25") (pinfunction "PC5_25") (pintype "bidirectional"))
    )
    (net (code "72") (name "unconnected-(U7-PC7-Pad38)") (class "Default")
      (node (ref "U7") (pin "38") (pinfunction "PC7_38") (pintype "bidirectional"))
    )
    (net (code "73") (name "unconnected-(U7-PC8-Pad39)") (class "Default")
      (node (ref "U7") (pin "39") (pinfunction "PC8_39") (pintype "bidirectional"))
    )
    (net (code "74") (name "unconnected-(U7-PC9-Pad40)") (class "Default")
      (node (ref "U7") (pin "40") (pinfunction "PC9_40") (pintype "bidirectional"))
    )
    (net (code "75") (name "unconnected-(U7-PC10-Pad51)") (class "Default")
      (node (ref "U7") (pin "51") (pinfunction "PC10_51") (pintype "bidirectional"))
    )
    (net (code "76") (name "unconnected-(U7-PC11-Pad52)") (class "Default")
      (node (ref "U7") (pin "52") (pinfunction "PC11_52") (pintype "bidirectional"))
    )
    (net (code "77") (name "unconnected-(U7-PC13-TAMPER-RTC-Pad2)") (class "Default")
      (node (ref "U7") (pin "2") (pinfunction "PC13-TAMPER-RTC_2") (pintype "bidirectional"))
    )
    (net (code "78") (name "unconnected-(U7-PC14-OSC32_IN-Pad3)") (class "Default")
      (node (ref "U7") (pin "3") (pinfunction "PC14-OSC32_IN_3") (pintype "bidirectional"))
    )
    (net (code "79") (name "unconnected-(U7-PC15-OSC32_OUT-Pad4)") (class "Default")
      (node (ref "U7") (pin "4") (pinfunction "PC15-OSC32_OUT_4") (pintype "bidirectional"))
    )
    (net (code "80") (name "unconnected-(U7-PD2-Pad54)") (class "Default")
      (node (ref "U7") (pin "54") (pinfunction "PD2_54") (pintype "bidirectional"))
    )
    (net (code "81") (name "unconnected-(U8-n.c.-Pad5)") (class "Default")
      (node (ref "U8") (pin "5") (pinfunction "n.c._5") (pintype "passive"))
    )
  )
)
